# gacun.net
KiCad netlist of a schematic drawn in EAGLE
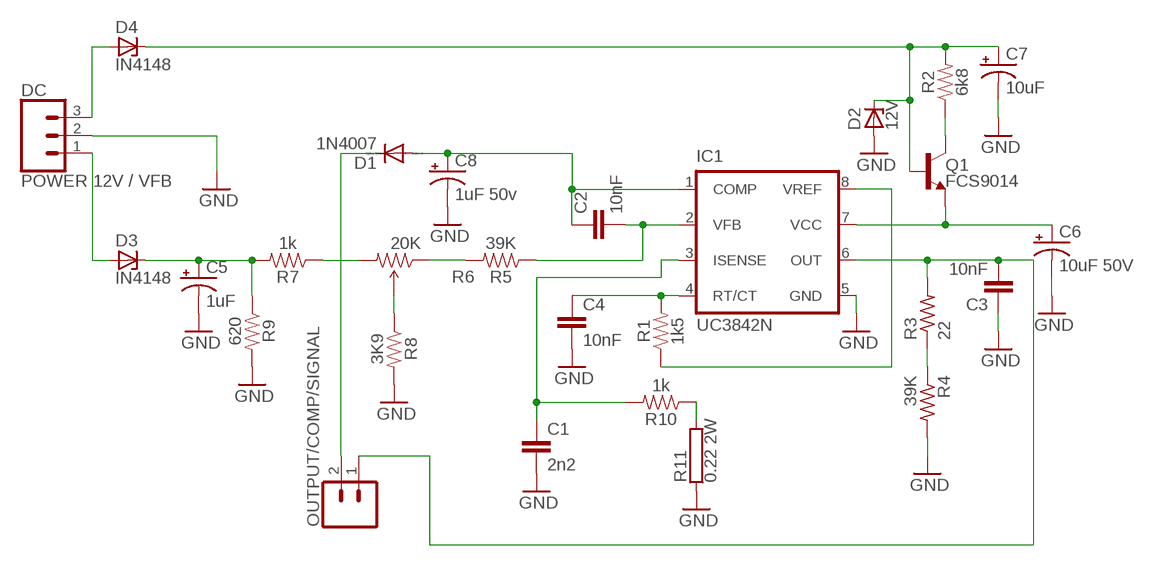
[diagram p0: schematic, sheet 1]

(export (version "E")
  (design (tool "Eeschema 10.0.6"))
  (components
    (comp (ref "C1")
      (value "2n2")
      (footprint "eagle-import:CAP-PTH-10MM")
      (libsource (lib "eagle-import") (part "10NF-PTH-10MM-10000V-1-%"))
    )
    (comp (ref "C2")
      (value "10nF")
      (footprint "eagle-import:CAP-PTH-10MM")
      (libsource (lib "eagle-import") (part "10NF-PTH-10MM-10000V-1-%"))
    )
    (comp (ref "C3")
      (value "10nF")
      (footprint "eagle-import:CAP-PTH-10MM")
      (libsource (lib "eagle-import") (part "10NF-PTH-10MM-10000V-1-%"))
    )
    (comp (ref "C4")
      (value "10nF")
      (footprint "eagle-import:CAP-PTH-10MM")
      (libsource (lib "eagle-import") (part "10NF-PTH-10MM-10000V-1-%"))
    )
    (comp (ref "C5")
      (value "1uF")
      (footprint "eagle-import:CPOL-RADIAL-2.5MM-5MM")
      (libsource (lib "eagle-import") (part "10UF-POLAR-RADIAL-2.5MM-25V-20%"))
    )
    (comp (ref "C6")
      (value "10uF 50V")
      (footprint "eagle-import:E2-4")
      (libsource (lib "eagle-import") (part "CPOL-USE2-4"))
    )
    (comp (ref "C7")
      (value "10uF")
      (footprint "eagle-import:CPOL-RADIAL-2.5MM-5MM")
      (libsource (lib "eagle-import") (part "10UF-POLAR-RADIAL-2.5MM-25V-20%"))
    )
    (comp (ref "C8")
      (value "1uF 50v")
      (footprint "eagle-import:CPOL-RADIAL-2.5MM-5MM")
      (libsource (lib "eagle-import") (part "10UF-POLAR-RADIAL-2.5MM-25V-20%"))
    )
    (comp (ref "D1")
      (value "1N4007")
      (footprint "eagle-import:DO41-10")
      (libsource (lib "eagle-import") (part "1N4004"))
    )
    (comp (ref "D2")
      (value "12V")
      (footprint "eagle-import:ZDIO-7.5")
      (libsource (lib "eagle-import") (part "ZENER-DIODEZD-7.5"))
    )
    (comp (ref "D3")
      (value "IN4148")
      (footprint "eagle-import:ZDIO-7.5")
      (libsource (lib "eagle-import") (part "ZENER-DIODEZD-7.5"))
    )
    (comp (ref "D4")
      (value "IN4148")
      (footprint "eagle-import:ZDIO-7.5")
      (libsource (lib "eagle-import") (part "ZENER-DIODEZD-7.5"))
    )
    (comp (ref "DC")
      (value "POWER 12V / VFB")
      (footprint "eagle-import:1X03")
      (libsource (lib "eagle-import") (part "CONN_03"))
    )
    (comp (ref "IC1")
      (value "UC3842N")
      (footprint "eagle-import:DIL08")
      (libsource (lib "eagle-import") (part "UC384N2"))
    )
    (comp (ref "OUTPUT/COMP/SIGNAL")
      (value "CONN_02")
      (footprint "eagle-import:1X02")
      (libsource (lib "eagle-import") (part "CONN_02"))
    )
    (comp (ref "Q1")
      (value "FCS9014")
      (footprint "eagle-import:TO-92-EZ")
      (libsource (lib "eagle-import") (part "TRANS_NPN-2N3904-EZ"))
    )
    (comp (ref "R1")
      (value "1k5")
      (footprint "eagle-import:AXIAL-0.3")
      (libsource (lib "eagle-import") (part "1KOHM-HORIZ-1/4W-1%"))
    )
    (comp (ref "R2")
      (value "6k8")
      (footprint "eagle-import:AXIAL-0.3")
      (libsource (lib "eagle-import") (part "1KOHM-HORIZ-1/4W-1%"))
    )
    (comp (ref "R3")
      (value "22")
      (footprint "eagle-import:0204_7")
      (libsource (lib "eagle-import") (part "R-US_0204/7"))
    )
    (comp (ref "R4")
      (value "39K")
      (footprint "eagle-import:0204_7")
      (libsource (lib "eagle-import") (part "R-US_0204/7"))
    )
    (comp (ref "R5")
      (value "39K")
      (footprint "eagle-import:AXIAL-0.3")
      (libsource (lib "eagle-import") (part "1KOHM-HORIZ-1/4W-1%"))
    )
    (comp (ref "R6")
      (value "20K")
      (footprint "eagle-import:TRIM_POT_PTH")
      (libsource (lib "eagle-import") (part "TRIMPOTPTH"))
    )
    (comp (ref "R7")
      (value "1k")
      (footprint "eagle-import:AXIAL-0.3")
      (libsource (lib "eagle-import") (part "1KOHM-HORIZ-1/4W-1%"))
    )
    (comp (ref "R8")
      (value "3K9")
      (footprint "eagle-import:AXIAL-0.3")
      (libsource (lib "eagle-import") (part "1KOHM-HORIZ-1/4W-1%"))
    )
    (comp (ref "R9")
      (value "620")
      (footprint "eagle-import:AXIAL-0.3")
      (libsource (lib "eagle-import") (part "1KOHM-HORIZ-1/4W-1%"))
    )
    (comp (ref "R10")
      (value "1k")
      (footprint "eagle-import:AXIAL-0.3")
      (libsource (lib "eagle-import") (part "1KOHM-HORIZ-1/4W-1%"))
    )
    (comp (ref "R11")
      (value "0.22 2W")
      (footprint "eagle-import:KH206-8")
      (libsource (lib "eagle-import") (part "RKH206-8"))
    )
  )
  (nets
    (net (code "1") (name "GND") (class "Default")
      (node (ref "C1") (pin "2") (pinfunction "2_2") (pintype "passive"))
      (node (ref "C3") (pin "1") (pinfunction "1_1") (pintype "passive"))
      (node (ref "C4") (pin "2") (pinfunction "2_2") (pintype "passive"))
      (node (ref "C5") (pin "2") (pinfunction "-_2") (pintype "passive"))
      (node (ref "C6") (pin "-") (pinfunction "-_-") (pintype "passive"))
      (node (ref "C7") (pin "2") (pinfunction "-_2") (pintype "passive"))
      (node (ref "C8") (pin "2") (pinfunction "-_2") (pintype "passive"))
      (node (ref "D2") (pin "A") (pinfunction "A_A") (pintype "passive"))
      (node (ref "DC") (pin "2") (pinfunction "2_2") (pintype "passive"))
      (node (ref "IC1") (pin "5") (pinfunction "GND_5") (pintype "power_in"))
      (node (ref "R11") (pin "1") (pinfunction "1_1") (pintype "passive"))
      (node (ref "R4") (pin "2") (pinfunction "2_2") (pintype "passive"))
      (node (ref "R8") (pin "P$2") (pinfunction "2_P$2") (pintype "passive"))
      (node (ref "R9") (pin "P$2") (pinfunction "2_P$2") (pintype "passive"))
    )
    (net (code "2") (name "Net-(C5-+)") (class "Default")
      (node (ref "C5") (pin "1") (pinfunction "+_1") (pintype "passive"))
      (node (ref "D3") (pin "C") (pinfunction "C_C") (pintype "passive"))
      (node (ref "R7") (pin "P$2") (pinfunction "2_P$2") (pintype "passive"))
      (node (ref "R9") (pin "P$1") (pinfunction "1_P$1") (pintype "passive"))
    )
    (net (code "3") (name "Net-(C7-+)") (class "Default")
      (node (ref "C7") (pin "1") (pinfunction "+_1") (pintype "passive"))
      (node (ref "D2") (pin "C") (pinfunction "C_C") (pintype "passive"))
      (node (ref "D4") (pin "C") (pinfunction "C_C") (pintype "passive"))
      (node (ref "Q1") (pin "2") (pinfunction "B_2") (pintype "passive"))
      (node (ref "R2") (pin "P$2") (pinfunction "2_P$2") (pintype "passive"))
    )
    (net (code "4") (name "Net-(C8-+)") (class "Default")
      (node (ref "C2") (pin "1") (pinfunction "1_1") (pintype "passive"))
      (node (ref "C8") (pin "1") (pinfunction "+_1") (pintype "passive"))
      (node (ref "D1") (pin "A") (pinfunction "A_A") (pintype "passive"))
      (node (ref "IC1") (pin "1") (pinfunction "COMP_1") (pintype "passive"))
    )
    (net (code "5") (name "Net-(D1-PadC)") (class "Default")
      (node (ref "D1") (pin "C") (pinfunction "C_C") (pintype "passive"))
      (node (ref "OUTPUT/COMP/SIGNAL") (pin "2") (pinfunction "2_2") (pintype "passive"))
    )
    (net (code "6") (name "Net-(D3-PadA)") (class "Default")
      (node (ref "D3") (pin "A") (pinfunction "A_A") (pintype "passive"))
      (node (ref "DC") (pin "1") (pinfunction "1_1") (pintype "passive"))
    )
    (net (code "7") (name "Net-(D4-PadA)") (class "Default")
      (node (ref "D4") (pin "A") (pinfunction "A_A") (pintype "passive"))
      (node (ref "DC") (pin "3") (pinfunction "3_3") (pintype "passive"))
    )
    (net (code "8") (name "Net-(IC1-ISENSE)") (class "Default")
      (node (ref "C1") (pin "1") (pinfunction "1_1") (pintype "passive"))
      (node (ref "IC1") (pin "3") (pinfunction "ISENSE_3") (pintype "input"))
      (node (ref "R10") (pin "P$2") (pinfunction "2_P$2") (pintype "passive"))
    )
    (net (code "9") (name "Net-(IC1-OUT)") (class "Default")
      (node (ref "C3") (pin "2") (pinfunction "2_2") (pintype "passive"))
      (node (ref "IC1") (pin "6") (pinfunction "OUT_6") (pintype "output"))
      (node (ref "OUTPUT/COMP/SIGNAL") (pin "1") (pinfunction "1_1") (pintype "passive"))
      (node (ref "R3") (pin "2") (pinfunction "2_2") (pintype "passive"))
    )
    (net (code "10") (name "Net-(IC1-RT{slash}CT)") (class "Default")
      (node (ref "C4") (pin "1") (pinfunction "1_1") (pintype "passive"))
      (node (ref "IC1") (pin "4") (pinfunction "RT/CT_4") (pintype "passive"))
      (node (ref "R1") (pin "P$2") (pinfunction "2_P$2") (pintype "passive"))
    )
    (net (code "11") (name "Net-(IC1-VCC)") (class "Default")
      (node (ref "C6") (pin "+") (pinfunction "+_+") (pintype "passive"))
      (node (ref "IC1") (pin "7") (pinfunction "VCC_7") (pintype "power_in"))
      (node (ref "Q1") (pin "1") (pinfunction "E_1") (pintype "passive"))
    )
    (net (code "12") (name "Net-(IC1-VFB)") (class "Default")
      (node (ref "C2") (pin "2") (pinfunction "2_2") (pintype "passive"))
      (node (ref "IC1") (pin "2") (pinfunction "VFB_2") (pintype "input"))
      (node (ref "R5") (pin "P$1") (pinfunction "1_P$1") (pintype "passive"))
    )
    (net (code "13") (name "Net-(IC1-VREF)") (class "Default")
      (node (ref "IC1") (pin "8") (pinfunction "VREF_8") (pintype "passive"))
      (node (ref "R1") (pin "P$1") (pinfunction "1_P$1") (pintype "passive"))
    )
    (net (code "14") (name "Net-(Q1-C)") (class "Default")
      (node (ref "Q1") (pin "3") (pinfunction "C_3") (pintype "passive"))
      (node (ref "R2") (pin "P$1") (pinfunction "1_P$1") (pintype "passive"))
    )
    (net (code "15") (name "Net-(R3-Pad1)") (class "Default")
      (node (ref "R3") (pin "1") (pinfunction "1_1") (pintype "passive"))
      (node (ref "R4") (pin "1") (pinfunction "1_1") (pintype "passive"))
    )
    (net (code "16") (name "Net-(R5-2)") (class "Default")
      (node (ref "R5") (pin "P$2") (pinfunction "2_P$2") (pintype "passive"))
      (node (ref "R6") (pin "1") (pinfunction "CCW_1") (pintype "passive"))
    )
    (net (code "17") (name "Net-(R6-CW)") (class "Default")
      (node (ref "R6") (pin "3") (pinfunction "CW_3") (pintype "passive"))
      (node (ref "R7") (pin "P$1") (pinfunction "1_P$1") (pintype "passive"))
    )
    (net (code "18") (name "Net-(R6-WIPER)") (class "Default")
      (node (ref "R6") (pin "2") (pinfunction "WIPER_2") (pintype "passive"))
      (node (ref "R8") (pin "P$1") (pinfunction "1_P$1") (pintype "passive"))
    )
    (net (code "19") (name "Net-(R10-1)") (class "Default")
      (node (ref "R10") (pin "P$1") (pinfunction "1_P$1") (pintype "passive"))
      (node (ref "R11") (pin "2") (pinfunction "2_2") (pintype "passive"))
    )
  )
)
